# Addon-LAN-WLAN-without-MAPLE_or-OneWire_.net
KiCad netlist of a schematic drawn in EAGLE
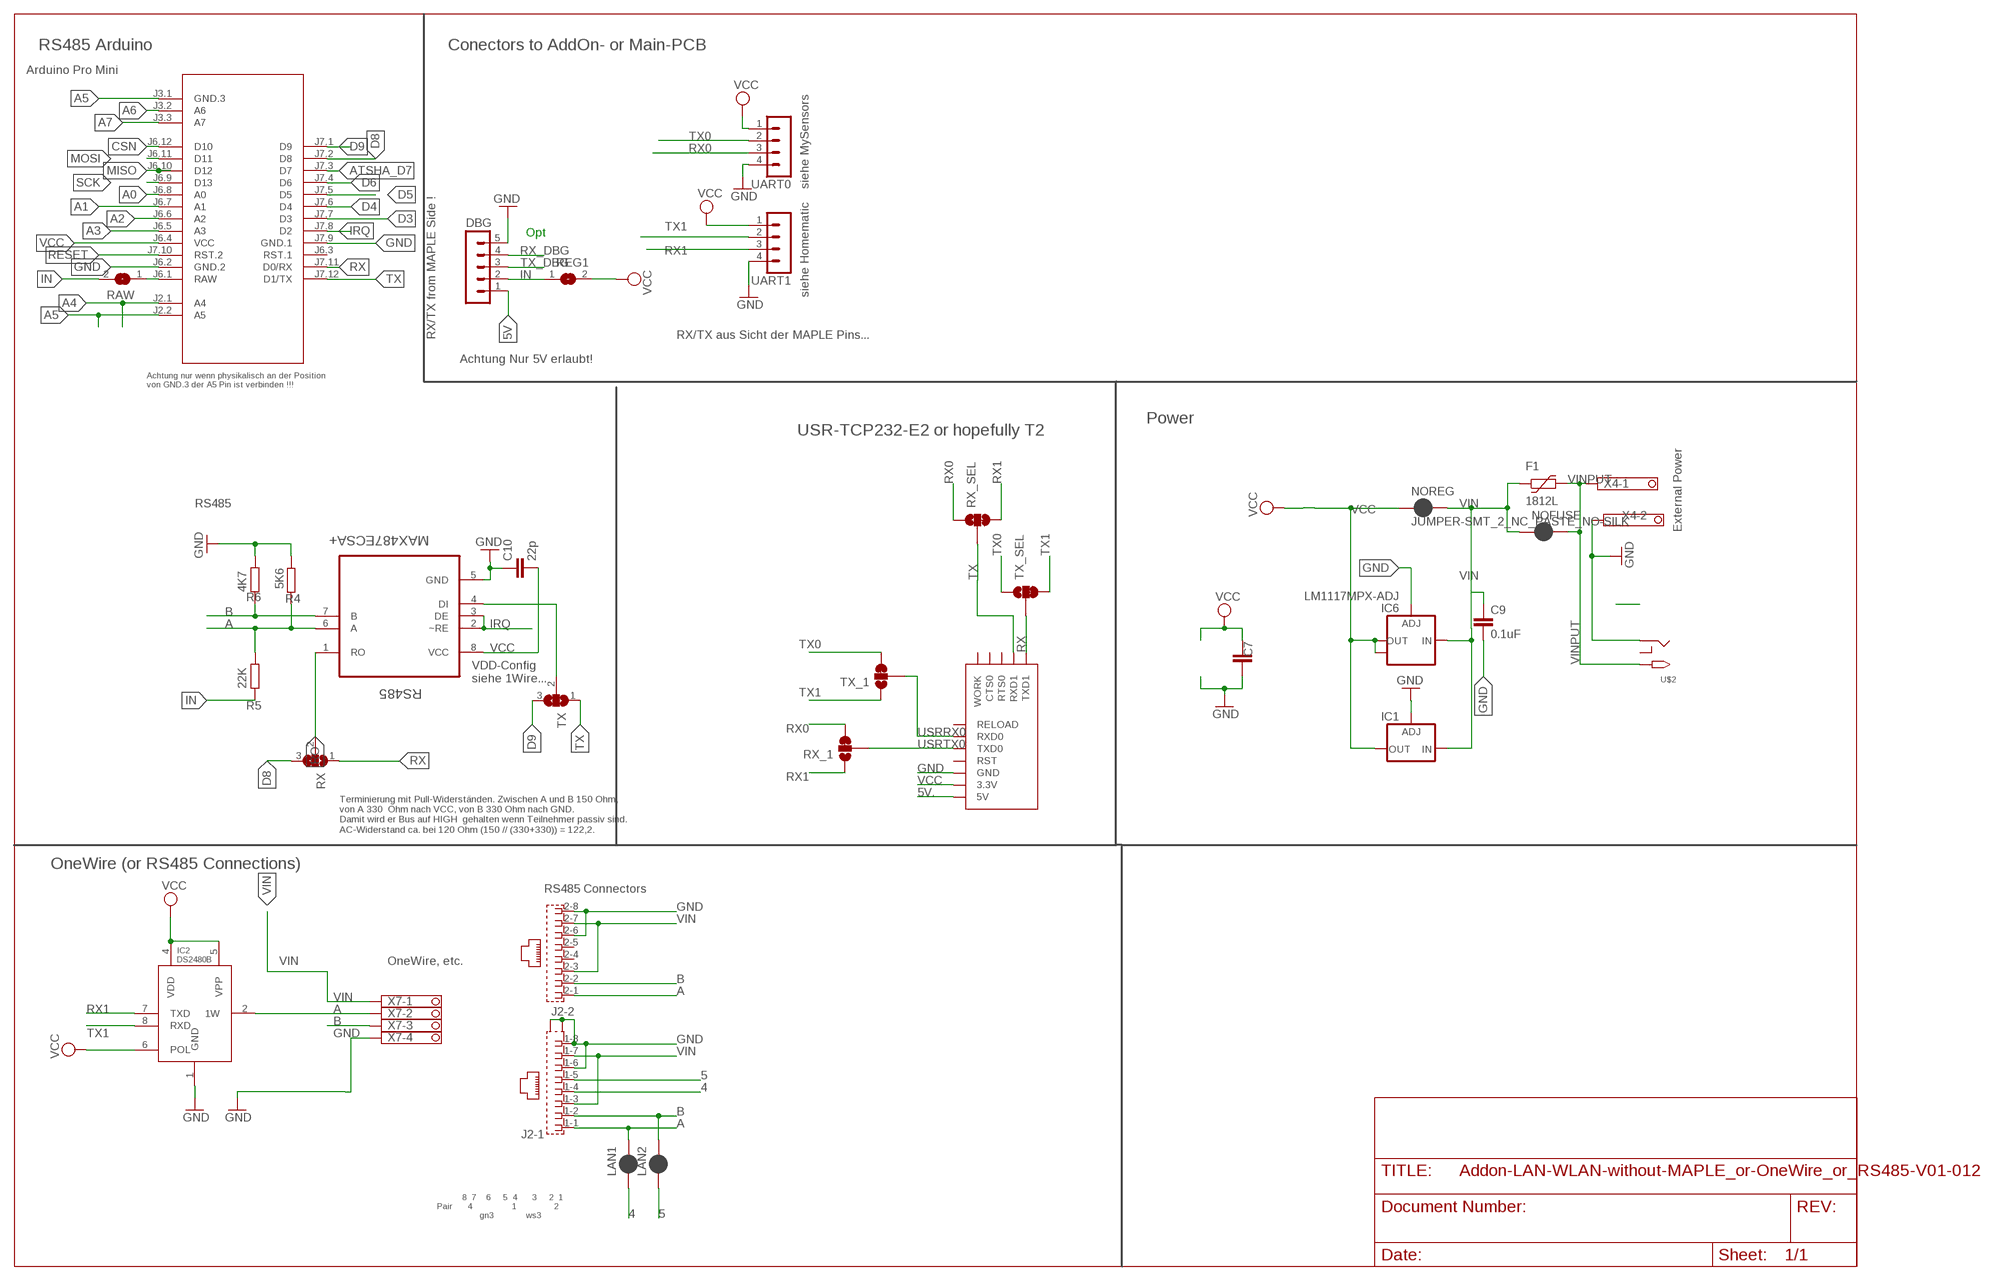
[diagram p0: schematic, sheet 1]

(export (version "E")
  (design (tool "Eeschema 10.0.6"))
  (components
    (comp (ref "C7")
      (value "C-EUC1812")
      (footprint "eagle-import:C1812")
      (libsource (lib "eagle-import") (part "rcl_334_C-EUC1812"))
    )
    (comp (ref "C9")
      (value "0.1uF")
      (footprint "eagle-import:C1206")
      (libsource (lib "eagle-import") (part "rcl_334_C-EUC1206"))
    )
    (comp (ref "C10")
      (value "22p")
      (footprint "eagle-import:C0805")
      (libsource (lib "eagle-import") (part "C-EUC0805"))
    )
    (comp (ref "DBG")
      (value "MA05-1")
      (footprint "eagle-import:MA05-1")
      (libsource (lib "eagle-import") (part "MA05-1"))
    )
    (comp (ref "F1")
      (value "1812L")
      (footprint "eagle-import:1812L")
      (libsource (lib "eagle-import") (part "1812L"))
    )
    (comp (ref "IC1")
      (value "LD117ADT50TR")
      (footprint "eagle-import:DPACK")
      (libsource (lib "eagle-import") (part "LD117A?DT50TR"))
    )
    (comp (ref "IC2")
      (value "DS2480B")
      (footprint "eagle-import:SO08")
      (libsource (lib "eagle-import") (part "DS2480B"))
    )
    (comp (ref "IC6")
      (value "LM1117MPX-ADJ")
      (footprint "eagle-import:SOT223")
      (libsource (lib "eagle-import") (part "LM1117MPX-ADJ"))
    )
    (comp (ref "J2")
      (value "RJ45_2X_S")
      (footprint "eagle-import:RJ45_2X_S")
      (libsource (lib "eagle-import") (part "RJ45_2X_S"))
    )
    (comp (ref "LAN1")
      (value "JUMPER-SMT_2_NC_PASTE_SILK")
      (footprint "eagle-import:SMT-JUMPER_2_NC_PASTE_SILK")
      (libsource (lib "eagle-import") (part "JUMPER-SMT_2_NC_PASTE_SILK"))
    )
    (comp (ref "LAN2")
      (value "JUMPER-SMT_2_NC_PASTE_SILK")
      (footprint "eagle-import:SMT-JUMPER_2_NC_PASTE_SILK")
      (libsource (lib "eagle-import") (part "JUMPER-SMT_2_NC_PASTE_SILK"))
    )
    (comp (ref "M1")
      (value "ARDUINO-PRO-MINI-3.3V#NP")
      (footprint "eagle-import:ARDUINO-PRO-MINI#NP")
      (libsource (lib "eagle-import") (part "ARDUINO-PRO-MINI-#NP3.3V"))
    )
    (comp (ref "NOFUSE")
      (value "JUMPER-SMT_2_NC_PASTE_NO-SILK")
      (footprint "eagle-import:SMT-JUMPER_2_NC_PASTE_NO-SILK")
      (libsource (lib "eagle-import") (part "JUMPER-SMT_2_NC_PASTE_NO-SILK"))
    )
    (comp (ref "NOREG")
      (value "JUMPER-SMT_2_NC_PASTE_NO-SILK")
      (footprint "eagle-import:SMT-JUMPER_2_NC_PASTE_NO-SILK")
      (libsource (lib "eagle-import") (part "SparkFun-Jumpers_528_JUMPER-SMT_2_NC_PASTE_NO-SILK"))
    )
    (comp (ref "R4")
      (value "5K6")
      (footprint "eagle-import:R0805")
      (libsource (lib "eagle-import") (part "R-EU_R0805"))
    )
    (comp (ref "R5")
      (value "22K")
      (footprint "eagle-import:R0805")
      (libsource (lib "eagle-import") (part "R-EU_R0805"))
    )
    (comp (ref "R6")
      (value "4K7")
      (footprint "eagle-import:R0805")
      (libsource (lib "eagle-import") (part "R-EU_R0805"))
    )
    (comp (ref "RAW") (value "SJ") (footprint "eagle-import:SJ") (libsource (lib "eagle-import") (part "SJ")))
    (comp (ref "REG1")
      (value "SJ")
      (footprint "eagle-import:SJ")
      (libsource (lib "eagle-import") (part "jumper_252_SJ"))
    )
    (comp (ref "RS485")
      (value "MAX487ECSA+")
      (footprint "eagle-import:SOIC127P600X175-8N")
      (libsource (lib "eagle-import") (part "MAX487ECSA+"))
    )
    (comp (ref "RX")
      (value "SJ2W")
      (footprint "eagle-import:SJ_2")
      (libsource (lib "eagle-import") (part "SJ2W"))
    )
    (comp (ref "RX_1")
      (value "JUMPER-SMT_3_1-NC_TRACE_SILK")
      (footprint "eagle-import:SMT-JUMPER_3_1-NC_TRACE_SILK")
      (libsource (lib "eagle-import") (part "JUMPER-SMT_3_1-NC_TRACE_SILK"))
    )
    (comp (ref "RX_SEL")
      (value "JUMPER-SMT_3_1-NC_TRACE_SILK")
      (footprint "eagle-import:SMT-JUMPER_3_1-NC_TRACE_SILK")
      (libsource (lib "eagle-import") (part "JUMPER-SMT_3_1-NC_TRACE_SILK"))
    )
    (comp (ref "TX")
      (value "SJ2W")
      (footprint "eagle-import:SJ_2")
      (libsource (lib "eagle-import") (part "SJ2W"))
    )
    (comp (ref "TX_1")
      (value "JUMPER-SMT_3_1-NC_TRACE_SILK")
      (footprint "eagle-import:SMT-JUMPER_3_1-NC_TRACE_SILK")
      (libsource (lib "eagle-import") (part "JUMPER-SMT_3_1-NC_TRACE_SILK"))
    )
    (comp (ref "TX_SEL")
      (value "JUMPER-SMT_3_1-NC_TRACE_SILK")
      (footprint "eagle-import:SMT-JUMPER_3_1-NC_TRACE_SILK")
      (libsource (lib "eagle-import") (part "JUMPER-SMT_3_1-NC_TRACE_SILK"))
    )
    (comp (ref "U$2")
      (value "2.1MMJACKTHM")
      (footprint "eagle-import:PJ-102A")
      (libsource (lib "eagle-import") (part "2.1MMJACKTHM"))
    )
    (comp (ref "U$5")
      (value "USR-TCP232-E2")
      (footprint "eagle-import:USR-TCP232-E2")
      (libsource (lib "eagle-import") (part "USR-TCP232-E2"))
    )
    (comp (ref "UART0")
      (value "MA04-1")
      (footprint "eagle-import:MA04-1")
      (libsource (lib "eagle-import") (part "MA04-1"))
    )
    (comp (ref "UART1")
      (value "MA04-1")
      (footprint "eagle-import:MA04-1")
      (libsource (lib "eagle-import") (part "MA04-1"))
    )
    (comp (ref "X4")
      (value "1751248")
      (footprint "eagle-import:1751248")
      (libsource (lib "eagle-import") (part "1751248"))
    )
    (comp (ref "X7")
      (value "1751264")
      (footprint "eagle-import:1751264")
      (libsource (lib "eagle-import") (part "1751264"))
    )
  )
  (nets
    (net (code "1") (name "/4") (class "Default")
      (node (ref "J2") (pin "1-4") (pinfunction "4_1-4") (pintype "passive"))
      (node (ref "LAN1") (pin "1") (pinfunction "1_1") (pintype "passive"))
    )
    (net (code "2") (name "/5") (class "Default")
      (node (ref "J2") (pin "1-5") (pinfunction "5_1-5") (pintype "passive"))
      (node (ref "LAN2") (pin "1") (pinfunction "1_1") (pintype "passive"))
    )
    (net (code "3") (name "/5V.") (class "Default")
      (node (ref "U$5") (pin "5V") (pinfunction "5V_5V") (pintype "bidirectional"))
    )
    (net (code "4") (name "/A") (class "Default")
      (node (ref "IC2") (pin "2") (pinfunction "1W_2") (pintype "open_collector"))
      (node (ref "J2") (pin "1-1") (pinfunction "1_1-1") (pintype "passive"))
      (node (ref "J2") (pin "2-1") (pinfunction "1_2-1") (pintype "passive"))
      (node (ref "LAN1") (pin "2") (pinfunction "2_2") (pintype "passive"))
      (node (ref "R4") (pin "2") (pinfunction "2_2") (pintype "passive"))
      (node (ref "R5") (pin "2") (pinfunction "2_2") (pintype "passive"))
      (node (ref "RS485") (pin "6") (pinfunction "A_6") (pintype "bidirectional"))
      (node (ref "X7") (pin "2") (pinfunction "K_2") (pintype "passive"))
    )
    (net (code "5") (name "/B") (class "Default")
      (node (ref "J2") (pin "1-2") (pinfunction "2_1-2") (pintype "passive"))
      (node (ref "J2") (pin "2-2") (pinfunction "2_2-2") (pintype "passive"))
      (node (ref "LAN2") (pin "2") (pinfunction "2_2") (pintype "passive"))
      (node (ref "R6") (pin "1") (pinfunction "1_1") (pintype "passive"))
      (node (ref "RS485") (pin "7") (pinfunction "B_7") (pintype "bidirectional"))
      (node (ref "X7") (pin "3") (pinfunction "K_3") (pintype "passive"))
    )
    (net (code "6") (name "/RX0") (class "Default")
      (node (ref "RX_1") (pin "3") (pinfunction "3_3") (pintype "passive"))
      (node (ref "RX_SEL") (pin "1") (pinfunction "1_1") (pintype "passive"))
      (node (ref "UART0") (pin "3") (pinfunction "3_3") (pintype "passive"))
    )
    (net (code "7") (name "/RX1") (class "Default")
      (node (ref "IC2") (pin "7") (pinfunction "TXD_7") (pintype "input"))
      (node (ref "RX_1") (pin "1") (pinfunction "1_1") (pintype "passive"))
      (node (ref "RX_SEL") (pin "3") (pinfunction "3_3") (pintype "passive"))
      (node (ref "UART1") (pin "3") (pinfunction "3_3") (pintype "passive"))
    )
    (net (code "8") (name "/RX_DBG") (class "Default")
      (node (ref "DBG") (pin "4") (pinfunction "4_4") (pintype "passive"))
    )
    (net (code "9") (name "/TX0") (class "Default")
      (node (ref "TX_1") (pin "3") (pinfunction "3_3") (pintype "passive"))
      (node (ref "TX_SEL") (pin "1") (pinfunction "1_1") (pintype "passive"))
      (node (ref "UART0") (pin "2") (pinfunction "2_2") (pintype "passive"))
    )
    (net (code "10") (name "/TX1") (class "Default")
      (node (ref "IC2") (pin "8") (pinfunction "RXD_8") (pintype "output"))
      (node (ref "TX_1") (pin "1") (pinfunction "1_1") (pintype "passive"))
      (node (ref "TX_SEL") (pin "3") (pinfunction "3_3") (pintype "passive"))
      (node (ref "UART1") (pin "2") (pinfunction "2_2") (pintype "passive"))
    )
    (net (code "11") (name "/TX_DBG") (class "Default")
      (node (ref "DBG") (pin "3") (pinfunction "3_3") (pintype "passive"))
    )
    (net (code "12") (name "/USRRX0") (class "Default")
      (node (ref "TX_1") (pin "2") (pinfunction "2_2") (pintype "passive"))
      (node (ref "U$5") (pin "RXD0") (pinfunction "RXD0_RXD0") (pintype "input"))
    )
    (net (code "13") (name "/USRTX0") (class "Default")
      (node (ref "RX_1") (pin "2") (pinfunction "2_2") (pintype "passive"))
      (node (ref "U$5") (pin "TXD0") (pinfunction "TXD0_TXD0") (pintype "output"))
    )
    (net (code "14") (name "/VINPUT") (class "Default")
      (node (ref "F1") (pin "P$2") (pinfunction "2_P$2") (pintype "passive"))
      (node (ref "NOFUSE") (pin "2") (pinfunction "2_2") (pintype "passive"))
      (node (ref "U$2") (pin "TIP") (pinfunction "TIP_TIP") (pintype "bidirectional"))
      (node (ref "X4") (pin "1") (pinfunction "K_1") (pintype "passive"))
    )
    (net (code "15") (name "5V") (class "Default")
      (node (ref "DBG") (pin "1") (pinfunction "1_1") (pintype "passive"))
    )
    (net (code "16") (name "A0") (class "Default")
      (node (ref "M1") (pin "J6.8") (pinfunction "A0_J6.8") (pintype "bidirectional"))
    )
    (net (code "17") (name "A1") (class "Default")
      (node (ref "M1") (pin "J6.7") (pinfunction "A1_J6.7") (pintype "bidirectional"))
    )
    (net (code "18") (name "A2") (class "Default")
      (node (ref "M1") (pin "J6.6") (pinfunction "A2_J6.6") (pintype "bidirectional"))
    )
    (net (code "19") (name "A3") (class "Default")
      (node (ref "M1") (pin "J6.5") (pinfunction "A3_J6.5") (pintype "bidirectional"))
    )
    (net (code "20") (name "A4") (class "Default")
      (node (ref "M1") (pin "J2.1") (pinfunction "A4_J2.1") (pintype "bidirectional"))
    )
    (net (code "21") (name "A5") (class "Default")
      (node (ref "M1") (pin "J2.2") (pinfunction "A5_J2.2") (pintype "bidirectional"))
      (node (ref "M1") (pin "J3.1") (pinfunction "GND.3_J3.1") (pintype "bidirectional"))
    )
    (net (code "22") (name "A6") (class "Default")
      (node (ref "M1") (pin "J3.2") (pinfunction "A6_J3.2") (pintype "bidirectional"))
    )
    (net (code "23") (name "A7") (class "Default")
      (node (ref "M1") (pin "J3.3") (pinfunction "A7_J3.3") (pintype "bidirectional"))
    )
    (net (code "24") (name "ATSHA_D7") (class "Default")
      (node (ref "M1") (pin "J7.3") (pinfunction "D7_J7.3") (pintype "bidirectional"))
    )
    (net (code "25") (name "CSN") (class "Default")
      (node (ref "M1") (pin "J6.12") (pinfunction "D10_J6.12") (pintype "bidirectional"))
    )
    (net (code "26") (name "D3") (class "Default")
      (node (ref "M1") (pin "J7.7") (pinfunction "D3_J7.7") (pintype "bidirectional"))
    )
    (net (code "27") (name "D4") (class "Default")
      (node (ref "M1") (pin "J7.6") (pinfunction "D4_J7.6") (pintype "bidirectional"))
    )
    (net (code "28") (name "D5") (class "Default")
      (node (ref "M1") (pin "J7.5") (pinfunction "D5_J7.5") (pintype "bidirectional"))
    )
    (net (code "29") (name "D6") (class "Default")
      (node (ref "M1") (pin "J7.4") (pinfunction "D6_J7.4") (pintype "bidirectional"))
    )
    (net (code "30") (name "D8") (class "Default")
      (node (ref "M1") (pin "J7.2") (pinfunction "D8_J7.2") (pintype "bidirectional"))
      (node (ref "RX") (pin "3") (pinfunction "3_3") (pintype "passive"))
    )
    (net (code "31") (name "D9") (class "Default")
      (node (ref "M1") (pin "J7.1") (pinfunction "D9_J7.1") (pintype "bidirectional"))
      (node (ref "TX") (pin "3") (pinfunction "3_3") (pintype "passive"))
    )
    (net (code "32") (name "GND") (class "Default")
      (node (ref "C10") (pin "1") (pinfunction "1_1") (pintype "passive"))
      (node (ref "C7") (pin "1") (pinfunction "1_1") (pintype "passive"))
      (node (ref "C9") (pin "2") (pinfunction "2_2") (pintype "passive"))
      (node (ref "DBG") (pin "5") (pinfunction "5_5") (pintype "passive"))
      (node (ref "IC1") (pin "1") (pinfunction "ADJ_1") (pintype "input"))
      (node (ref "IC2") (pin "1") (pinfunction "GND_1") (pintype "power_in"))
      (node (ref "IC6") (pin "1") (pinfunction "ADJ_1") (pintype "input"))
      (node (ref "J2") (pin "1-6") (pinfunction "6_1-6") (pintype "passive"))
      (node (ref "J2") (pin "1-8") (pinfunction "8_1-8") (pintype "passive"))
      (node (ref "J2") (pin "2-6") (pinfunction "6_2-6") (pintype "passive"))
      (node (ref "J2") (pin "2-8") (pinfunction "8_2-8") (pintype "passive"))
      (node (ref "J2") (pin "G1") (pinfunction "S2_G1") (pintype "passive"))
      (node (ref "J2") (pin "G3") (pinfunction "S1_G3") (pintype "passive"))
      (node (ref "M1") (pin "J6.2") (pinfunction "GND.2_J6.2") (pintype "power_in"))
      (node (ref "M1") (pin "J7.9") (pinfunction "GND.1_J7.9") (pintype "power_in"))
      (node (ref "R4") (pin "1") (pinfunction "1_1") (pintype "passive"))
      (node (ref "R6") (pin "2") (pinfunction "2_2") (pintype "passive"))
      (node (ref "RS485") (pin "5") (pinfunction "GND_5") (pintype "passive"))
      (node (ref "U$2") (pin "RING") (pinfunction "RING_RING") (pintype "bidirectional"))
      (node (ref "U$5") (pin "GND") (pinfunction "GND_GND") (pintype "bidirectional"))
      (node (ref "UART0") (pin "4") (pinfunction "4_4") (pintype "passive"))
      (node (ref "UART1") (pin "4") (pinfunction "4_4") (pintype "passive"))
      (node (ref "X4") (pin "2") (pinfunction "K_2") (pintype "passive"))
      (node (ref "X7") (pin "4") (pinfunction "K_4") (pintype "passive"))
    )
    (net (code "33") (name "IN") (class "Default")
      (node (ref "DBG") (pin "2") (pinfunction "2_2") (pintype "passive"))
      (node (ref "R5") (pin "1") (pinfunction "1_1") (pintype "passive"))
      (node (ref "RAW") (pin "2") (pinfunction "2_2") (pintype "passive"))
      (node (ref "REG1") (pin "1") (pinfunction "1_1") (pintype "passive"))
    )
    (net (code "34") (name "IRQ") (class "Default")
      (node (ref "M1") (pin "J7.8") (pinfunction "D2_J7.8") (pintype "bidirectional"))
      (node (ref "RS485") (pin "2") (pinfunction "~{RE}_2") (pintype "input"))
      (node (ref "RS485") (pin "3") (pinfunction "DE_3") (pintype "input"))
    )
    (net (code "35") (name "MISO") (class "Default")
      (node (ref "M1") (pin "J6.10") (pinfunction "D12_J6.10") (pintype "bidirectional"))
    )
    (net (code "36") (name "MOSI") (class "Default")
      (node (ref "M1") (pin "J6.11") (pinfunction "D11_J6.11") (pintype "bidirectional"))
    )
    (net (code "37") (name "Net-(M1-RAW)") (class "Default")
      (node (ref "M1") (pin "J6.1") (pinfunction "RAW_J6.1") (pintype "power_in"))
      (node (ref "RAW") (pin "1") (pinfunction "1_1") (pintype "passive"))
    )
    (net (code "38") (name "Net-(RS485-DI)") (class "Default")
      (node (ref "RS485") (pin "4") (pinfunction "DI_4") (pintype "input"))
      (node (ref "TX") (pin "2") (pinfunction "2_2") (pintype "passive"))
    )
    (net (code "39") (name "RESET") (class "Default")
      (node (ref "M1") (pin "J7.10") (pinfunction "RST.2_J7.10") (pintype "bidirectional"))
    )
    (net (code "40") (name "RO") (class "Default")
      (node (ref "RS485") (pin "1") (pinfunction "RO_1") (pintype "output"))
      (node (ref "RX") (pin "2") (pinfunction "2_2") (pintype "passive"))
    )
    (net (code "41") (name "RX") (class "Default")
      (node (ref "M1") (pin "J7.11") (pinfunction "D0/RX_J7.11") (pintype "bidirectional"))
      (node (ref "RX") (pin "1") (pinfunction "1_1") (pintype "passive"))
      (node (ref "TX_SEL") (pin "2") (pinfunction "2_2") (pintype "passive"))
      (node (ref "U$5") (pin "TXD1") (pinfunction "TXD1_TXD1") (pintype "output"))
    )
    (net (code "42") (name "SCK") (class "Default")
      (node (ref "M1") (pin "J6.9") (pinfunction "D13_J6.9") (pintype "bidirectional"))
    )
    (net (code "43") (name "TX") (class "Default")
      (node (ref "M1") (pin "J7.12") (pinfunction "D1/TX_J7.12") (pintype "bidirectional"))
      (node (ref "RX_SEL") (pin "2") (pinfunction "2_2") (pintype "passive"))
      (node (ref "TX") (pin "1") (pinfunction "1_1") (pintype "passive"))
      (node (ref "U$5") (pin "RXD1") (pinfunction "RXD1_RXD1") (pintype "input"))
    )
    (net (code "44") (name "VCC") (class "Default")
      (node (ref "C10") (pin "2") (pinfunction "2_2") (pintype "passive"))
      (node (ref "C7") (pin "2") (pinfunction "2_2") (pintype "passive"))
      (node (ref "IC1") (pin "4") (pinfunction "OUT_4") (pintype "passive"))
      (node (ref "IC2") (pin "4") (pinfunction "VDD_4") (pintype "power_in"))
      (node (ref "IC2") (pin "5") (pinfunction "VPP_5") (pintype "power_in"))
      (node (ref "IC2") (pin "6") (pinfunction "POL_6") (pintype "input"))
      (node (ref "IC6") (pin "2") (pinfunction "OUT_2") (pintype "passive"))
      (node (ref "IC6") (pin "TAB") (pinfunction "OUT1_TAB") (pintype "passive"))
      (node (ref "M1") (pin "J6.4") (pinfunction "VCC_J6.4") (pintype "power_in"))
      (node (ref "NOREG") (pin "1") (pinfunction "1_1") (pintype "passive"))
      (node (ref "REG1") (pin "2") (pinfunction "2_2") (pintype "passive"))
      (node (ref "RS485") (pin "8") (pinfunction "VCC_8") (pintype "power_in"))
      (node (ref "U$5") (pin "3.3V") (pinfunction "3.3V_3.3V") (pintype "bidirectional"))
      (node (ref "UART0") (pin "1") (pinfunction "1_1") (pintype "passive"))
      (node (ref "UART1") (pin "1") (pinfunction "1_1") (pintype "passive"))
    )
    (net (code "45") (name "VIN") (class "Default")
      (node (ref "C9") (pin "1") (pinfunction "1_1") (pintype "passive"))
      (node (ref "F1") (pin "P$1") (pinfunction "1_P$1") (pintype "passive"))
      (node (ref "IC1") (pin "3") (pinfunction "IN_3") (pintype "input"))
      (node (ref "IC6") (pin "3") (pinfunction "IN_3") (pintype "input"))
      (node (ref "J2") (pin "1-3") (pinfunction "3_1-3") (pintype "passive"))
      (node (ref "J2") (pin "1-7") (pinfunction "7_1-7") (pintype "passive"))
      (node (ref "J2") (pin "2-3") (pinfunction "3_2-3") (pintype "passive"))
      (node (ref "J2") (pin "2-7") (pinfunction "7_2-7") (pintype "passive"))
      (node (ref "NOFUSE") (pin "1") (pinfunction "1_1") (pintype "passive"))
      (node (ref "NOREG") (pin "2") (pinfunction "2_2") (pintype "passive"))
      (node (ref "X7") (pin "1") (pinfunction "K_1") (pintype "passive"))
    )
    (net (code "46") (name "unconnected-(J2B-4-Pad2-4)") (class "Default")
      (node (ref "J2") (pin "2-4") (pinfunction "4_2-4") (pintype "passive"))
    )
    (net (code "47") (name "unconnected-(J2B-5-Pad2-5)") (class "Default")
      (node (ref "J2") (pin "2-5") (pinfunction "5_2-5") (pintype "passive"))
    )
    (net (code "48") (name "unconnected-(M1-RST.1-PadJ6.3)") (class "Default")
      (node (ref "M1") (pin "J6.3") (pinfunction "RST.1_J6.3") (pintype "bidirectional"))
    )
    (net (code "49") (name "unconnected-(U$2-PadRING_SW)") (class "Default")
      (node (ref "U$2") (pin "RING_SW") (pinfunction "RING_SW_RING_SW") (pintype "bidirectional"))
    )
    (net (code "50") (name "unconnected-(U$5-PadCTS0)") (class "Default")
      (node (ref "U$5") (pin "CTS0") (pinfunction "CTS0_CTS0") (pintype "bidirectional"))
    )
    (net (code "51") (name "unconnected-(U$5-PadRELOAD)") (class "Default")
      (node (ref "U$5") (pin "RELOAD") (pinfunction "RELOAD_RELOAD") (pintype "bidirectional"))
    )
    (net (code "52") (name "unconnected-(U$5-PadRST)") (class "Default")
      (node (ref "U$5") (pin "RST") (pinfunction "RST_RST") (pintype "bidirectional"))
    )
    (net (code "53") (name "unconnected-(U$5-PadRTS0)") (class "Default")
      (node (ref "U$5") (pin "RTS0") (pinfunction "RTS0_RTS0") (pintype "bidirectional"))
    )
    (net (code "54") (name "unconnected-(U$5-PadWORK)") (class "Default")
      (node (ref "U$5") (pin "WORK") (pinfunction "WORK_WORK") (pintype "bidirectional"))
    )
  )
)
